# RPi_Extension_adc.net
KiCad netlist of a schematic drawn in EAGLE
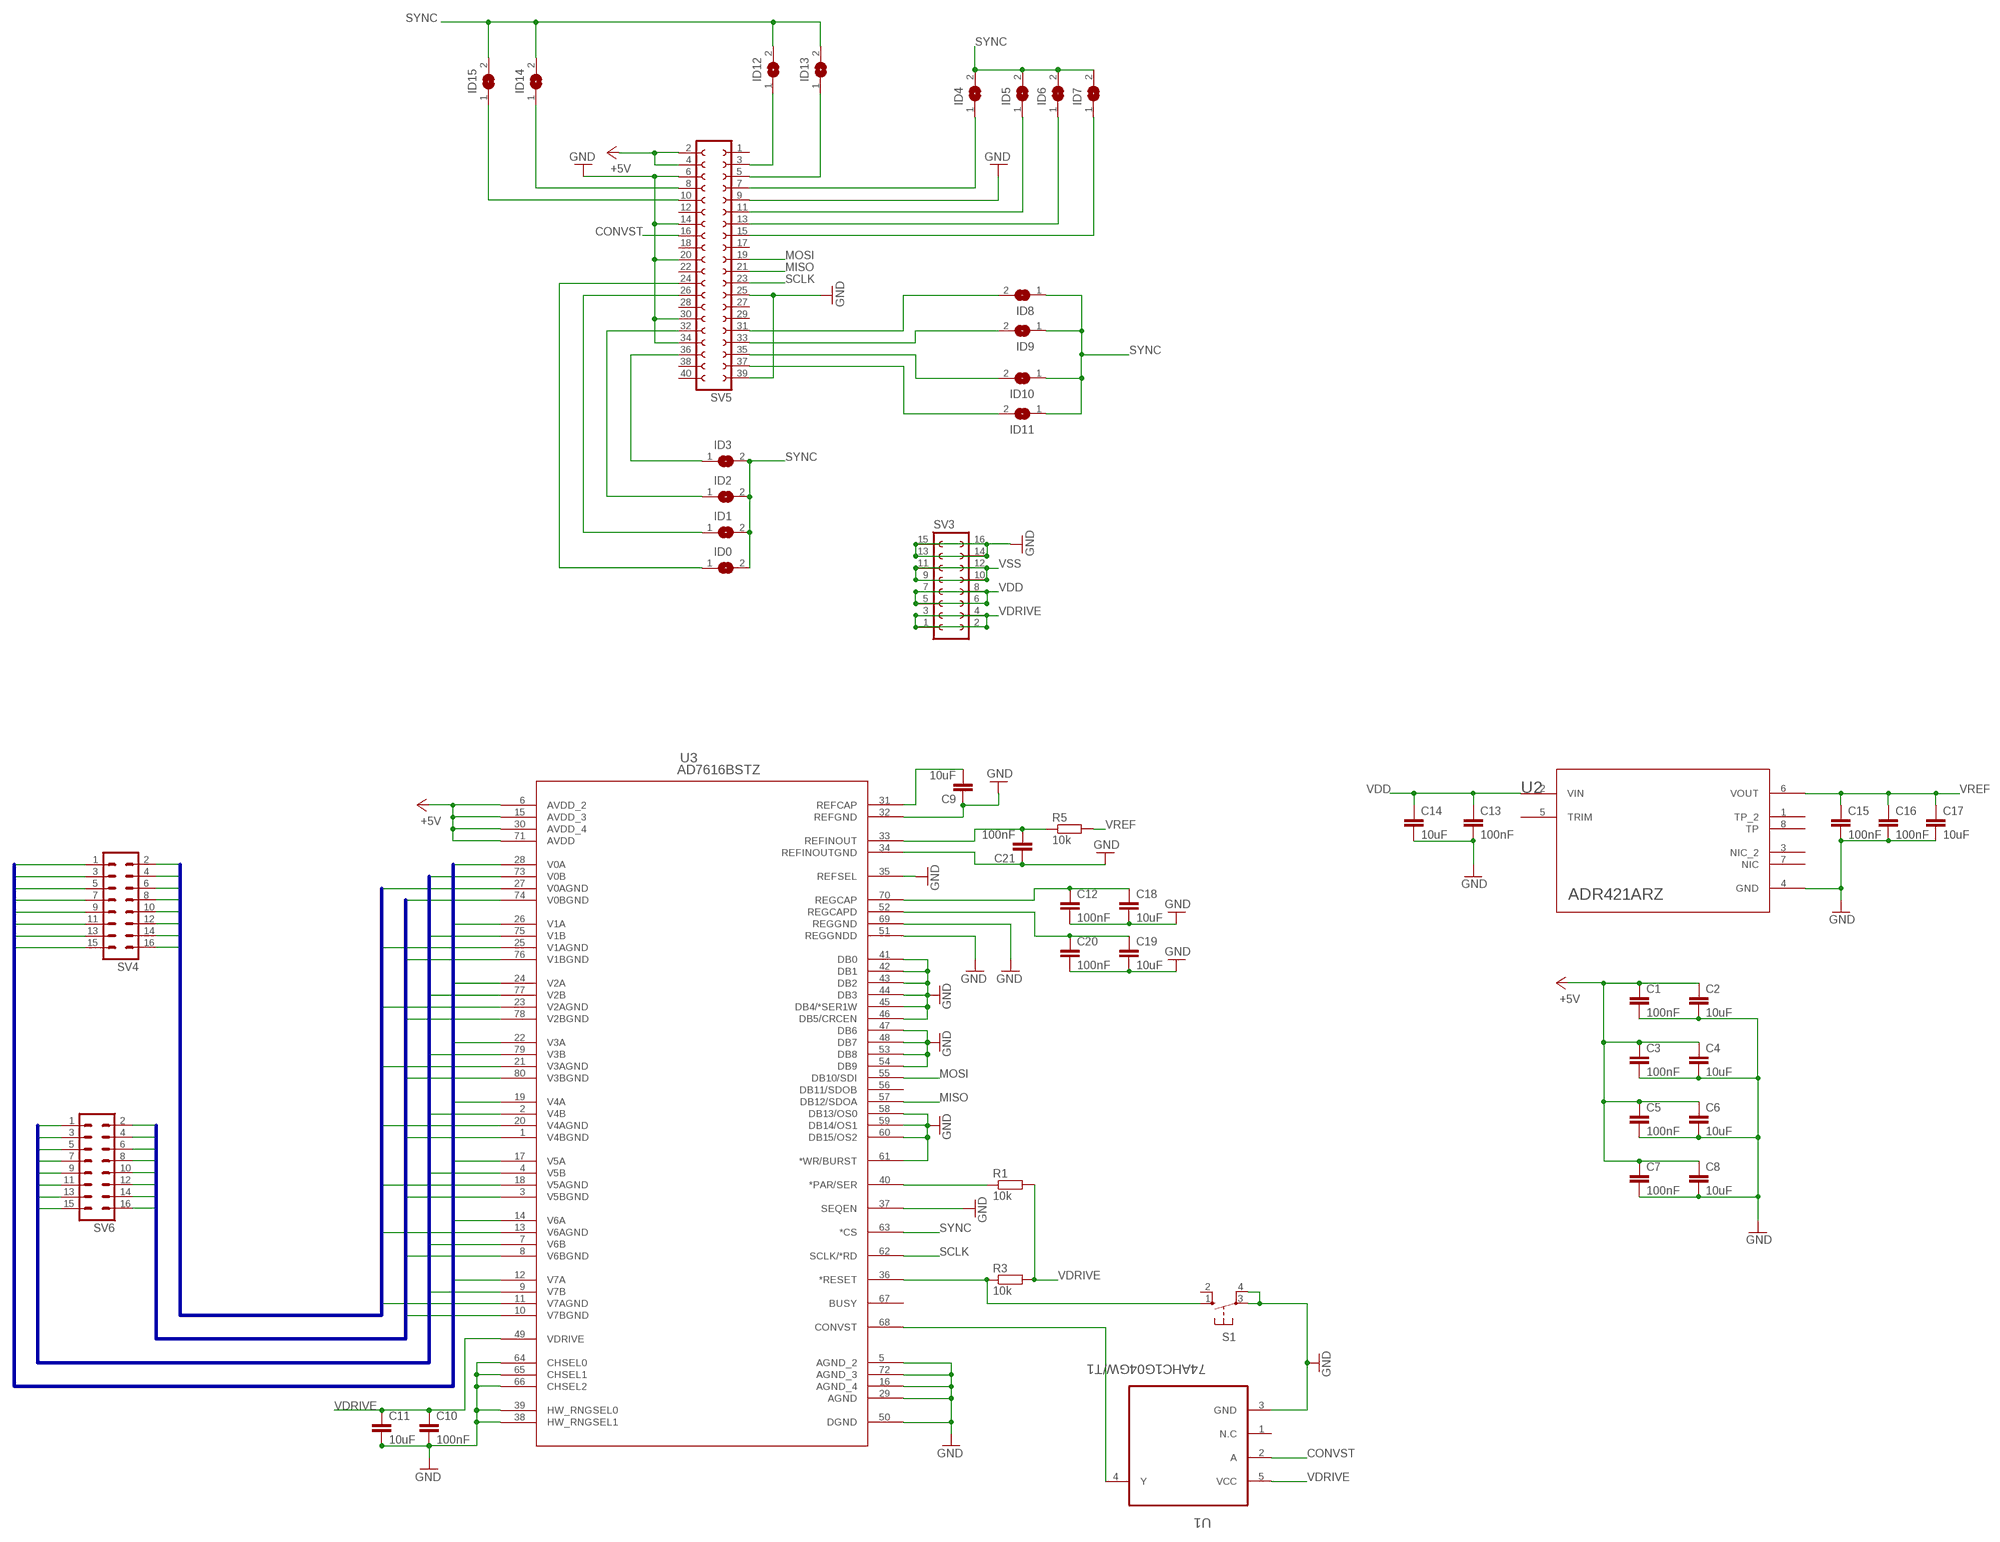
[diagram p0: schematic, sheet 1]

(export (version "E")
  (design (tool "Eeschema 10.0.6"))
  (components
    (comp (ref "C1")
      (value "100nF")
      (footprint "eagle-import:C0603")
      (libsource (lib "eagle-import") (part "C-EUC0603"))
    )
    (comp (ref "C2")
      (value "10uF")
      (footprint "eagle-import:C0603")
      (libsource (lib "eagle-import") (part "C-EUC0603"))
    )
    (comp (ref "C3")
      (value "100nF")
      (footprint "eagle-import:C0603")
      (libsource (lib "eagle-import") (part "C-EUC0603"))
    )
    (comp (ref "C4")
      (value "10uF")
      (footprint "eagle-import:C0603")
      (libsource (lib "eagle-import") (part "C-EUC0603"))
    )
    (comp (ref "C5")
      (value "100nF")
      (footprint "eagle-import:C0603")
      (libsource (lib "eagle-import") (part "C-EUC0603"))
    )
    (comp (ref "C6")
      (value "10uF")
      (footprint "eagle-import:C0603")
      (libsource (lib "eagle-import") (part "C-EUC0603"))
    )
    (comp (ref "C7")
      (value "100nF")
      (footprint "eagle-import:C0603")
      (libsource (lib "eagle-import") (part "C-EUC0603"))
    )
    (comp (ref "C8")
      (value "10uF")
      (footprint "eagle-import:C0603")
      (libsource (lib "eagle-import") (part "C-EUC0603"))
    )
    (comp (ref "C9")
      (value "10uF")
      (footprint "eagle-import:C0603")
      (libsource (lib "eagle-import") (part "C-EUC0603"))
    )
    (comp (ref "C10")
      (value "100nF")
      (footprint "eagle-import:C0603")
      (libsource (lib "eagle-import") (part "C-EUC0603"))
    )
    (comp (ref "C11")
      (value "10uF")
      (footprint "eagle-import:C0603")
      (libsource (lib "eagle-import") (part "C-EUC0603"))
    )
    (comp (ref "C12")
      (value "100nF")
      (footprint "eagle-import:C0603")
      (libsource (lib "eagle-import") (part "C-EUC0603"))
    )
    (comp (ref "C13")
      (value "100nF")
      (footprint "eagle-import:C0603")
      (libsource (lib "eagle-import") (part "C-EUC0603"))
    )
    (comp (ref "C14")
      (value "10uF")
      (footprint "eagle-import:C1206")
      (libsource (lib "eagle-import") (part "C-EUC1206"))
    )
    (comp (ref "C15")
      (value "100nF")
      (footprint "eagle-import:C0603")
      (libsource (lib "eagle-import") (part "C-EUC0603"))
    )
    (comp (ref "C16")
      (value "100nF")
      (footprint "eagle-import:C0603")
      (libsource (lib "eagle-import") (part "C-EUC0603"))
    )
    (comp (ref "C17")
      (value "10uF")
      (footprint "eagle-import:C1206")
      (libsource (lib "eagle-import") (part "C-EUC1206"))
    )
    (comp (ref "C18")
      (value "10uF")
      (footprint "eagle-import:C0603")
      (libsource (lib "eagle-import") (part "C-EUC0603"))
    )
    (comp (ref "C19")
      (value "10uF")
      (footprint "eagle-import:C0603")
      (libsource (lib "eagle-import") (part "C-EUC0603"))
    )
    (comp (ref "C20")
      (value "100nF")
      (footprint "eagle-import:C0603")
      (libsource (lib "eagle-import") (part "C-EUC0603"))
    )
    (comp (ref "C21")
      (value "100nF")
      (footprint "eagle-import:C0603")
      (libsource (lib "eagle-import") (part "C-EUC0603"))
    )
    (comp (ref "ID0") (value "SJ") (footprint "eagle-import:SJ") (libsource (lib "eagle-import") (part "SJ")))
    (comp (ref "ID1") (value "SJ") (footprint "eagle-import:SJ") (libsource (lib "eagle-import") (part "SJ")))
    (comp (ref "ID2") (value "SJ") (footprint "eagle-import:SJ") (libsource (lib "eagle-import") (part "SJ")))
    (comp (ref "ID3") (value "SJ") (footprint "eagle-import:SJ") (libsource (lib "eagle-import") (part "SJ")))
    (comp (ref "ID4") (value "SJ") (footprint "eagle-import:SJ") (libsource (lib "eagle-import") (part "SJ")))
    (comp (ref "ID5") (value "SJ") (footprint "eagle-import:SJ") (libsource (lib "eagle-import") (part "SJ")))
    (comp (ref "ID6") (value "SJ") (footprint "eagle-import:SJ") (libsource (lib "eagle-import") (part "SJ")))
    (comp (ref "ID7") (value "SJ") (footprint "eagle-import:SJ") (libsource (lib "eagle-import") (part "SJ")))
    (comp (ref "ID8") (value "SJ") (footprint "eagle-import:SJ") (libsource (lib "eagle-import") (part "SJ")))
    (comp (ref "ID9") (value "SJ") (footprint "eagle-import:SJ") (libsource (lib "eagle-import") (part "SJ")))
    (comp (ref "ID10")
      (value "SJ")
      (footprint "eagle-import:SJ")
      (libsource (lib "eagle-import") (part "SJ"))
    )
    (comp (ref "ID11")
      (value "SJ")
      (footprint "eagle-import:SJ")
      (libsource (lib "eagle-import") (part "SJ"))
    )
    (comp (ref "ID12")
      (value "SJ")
      (footprint "eagle-import:SJ")
      (libsource (lib "eagle-import") (part "SJ"))
    )
    (comp (ref "ID13")
      (value "SJ")
      (footprint "eagle-import:SJ")
      (libsource (lib "eagle-import") (part "SJ"))
    )
    (comp (ref "ID14")
      (value "SJ")
      (footprint "eagle-import:SJ")
      (libsource (lib "eagle-import") (part "SJ"))
    )
    (comp (ref "ID15")
      (value "SJ")
      (footprint "eagle-import:SJ")
      (libsource (lib "eagle-import") (part "SJ"))
    )
    (comp (ref "R1")
      (value "10k")
      (footprint "eagle-import:R0603")
      (libsource (lib "eagle-import") (part "R-EU_R0603"))
    )
    (comp (ref "R3")
      (value "10k")
      (footprint "eagle-import:R0603")
      (libsource (lib "eagle-import") (part "R-EU_R0603"))
    )
    (comp (ref "R5")
      (value "10k")
      (footprint "eagle-import:R0603")
      (libsource (lib "eagle-import") (part "R-EU_R0603"))
    )
    (comp (ref "S1")
      (value "10-XX")
      (footprint "eagle-import:B3F-10XX")
      (fields (field (name "MPN") "B3F-1000"))
      (libsource (lib "eagle-import") (part "10-XX"))
    )
    (comp (ref "SV3")
      (value "FE08-2")
      (footprint "eagle-import:FE08-2")
      (libsource (lib "eagle-import") (part "FE08-2"))
    )
    (comp (ref "SV4")
      (value "MA08-2W")
      (footprint "eagle-import:MA08-2W")
      (libsource (lib "eagle-import") (part "MA08-2W"))
    )
    (comp (ref "SV5")
      (value "FE20-2")
      (footprint "eagle-import:FE20-2")
      (libsource (lib "eagle-import") (part "FE20-2"))
    )
    (comp (ref "SV6")
      (value "MA08-2W")
      (footprint "eagle-import:MA08-2W")
      (libsource (lib "eagle-import") (part "MA08-2W"))
    )
    (comp (ref "U1")
      (value "74AHC1G04GW/T1")
      (footprint "eagle-import:SOT65P210X110-5N")
      (libsource (lib "eagle-import") (part "74AHC1G04GW/T1"))
    )
    (comp (ref "U2")
      (value "ADR421ARZ")
      (footprint "eagle-import:R_8")
      (fields (field (name "MANUFACTURER_PART_NUMBER") "ADR423ARZ"))
      (libsource (lib "eagle-import") (part "ADR423ARZ"))
    )
    (comp (ref "U3")
      (value "AD7616BSTZ")
      (footprint "eagle-import:ST_80_2")
      (libsource (lib "eagle-import") (part "AD7616BSTZ"))
    )
  )
  (nets
    (net (code "1") (name "+5V") (class "Default")
      (node (ref "C1") (pin "1") (pinfunction "1_1") (pintype "passive"))
      (node (ref "C2") (pin "1") (pinfunction "1_1") (pintype "passive"))
      (node (ref "C3") (pin "1") (pinfunction "1_1") (pintype "passive"))
      (node (ref "C4") (pin "1") (pinfunction "1_1") (pintype "passive"))
      (node (ref "C5") (pin "1") (pinfunction "1_1") (pintype "passive"))
      (node (ref "C6") (pin "1") (pinfunction "1_1") (pintype "passive"))
      (node (ref "C7") (pin "1") (pinfunction "1_1") (pintype "passive"))
      (node (ref "C8") (pin "1") (pinfunction "1_1") (pintype "passive"))
      (node (ref "SV5") (pin "2") (pinfunction "2_2") (pintype "passive"))
      (node (ref "SV5") (pin "4") (pinfunction "4_4") (pintype "passive"))
      (node (ref "U3") (pin "15") (pinfunction "AVDD_3_15") (pintype "passive"))
      (node (ref "U3") (pin "30") (pinfunction "AVDD_4_30") (pintype "passive"))
      (node (ref "U3") (pin "6") (pinfunction "AVDD_2_6") (pintype "passive"))
      (node (ref "U3") (pin "71") (pinfunction "AVDD_71") (pintype "passive"))
    )
    (net (code "2") (name "/CONVST") (class "Default")
      (node (ref "SV5") (pin "16") (pinfunction "16_16") (pintype "passive"))
      (node (ref "U1") (pin "2") (pinfunction "A_2") (pintype "input"))
    )
    (net (code "3") (name "/MISO") (class "Default")
      (node (ref "SV5") (pin "21") (pinfunction "21_21") (pintype "passive"))
      (node (ref "U3") (pin "57") (pinfunction "DB12/SDOA_57") (pintype "passive"))
    )
    (net (code "4") (name "/MOSI") (class "Default")
      (node (ref "SV5") (pin "19") (pinfunction "19_19") (pintype "passive"))
      (node (ref "U3") (pin "55") (pinfunction "DB10/SDI_55") (pintype "passive"))
    )
    (net (code "5") (name "/SCLK") (class "Default")
      (node (ref "SV5") (pin "23") (pinfunction "23_23") (pintype "passive"))
      (node (ref "U3") (pin "62") (pinfunction "SCLK/*RD_62") (pintype "passive"))
    )
    (net (code "6") (name "/SYNC") (class "Default")
      (node (ref "ID0") (pin "2") (pinfunction "2_2") (pintype "passive"))
      (node (ref "ID1") (pin "2") (pinfunction "2_2") (pintype "passive"))
      (node (ref "ID10") (pin "1") (pinfunction "1_1") (pintype "passive"))
      (node (ref "ID11") (pin "1") (pinfunction "1_1") (pintype "passive"))
      (node (ref "ID12") (pin "2") (pinfunction "2_2") (pintype "passive"))
      (node (ref "ID13") (pin "2") (pinfunction "2_2") (pintype "passive"))
      (node (ref "ID14") (pin "2") (pinfunction "2_2") (pintype "passive"))
      (node (ref "ID15") (pin "2") (pinfunction "2_2") (pintype "passive"))
      (node (ref "ID2") (pin "2") (pinfunction "2_2") (pintype "passive"))
      (node (ref "ID3") (pin "2") (pinfunction "2_2") (pintype "passive"))
      (node (ref "ID4") (pin "2") (pinfunction "2_2") (pintype "passive"))
      (node (ref "ID5") (pin "2") (pinfunction "2_2") (pintype "passive"))
      (node (ref "ID6") (pin "2") (pinfunction "2_2") (pintype "passive"))
      (node (ref "ID7") (pin "2") (pinfunction "2_2") (pintype "passive"))
      (node (ref "ID8") (pin "1") (pinfunction "1_1") (pintype "passive"))
      (node (ref "ID9") (pin "1") (pinfunction "1_1") (pintype "passive"))
      (node (ref "U3") (pin "63") (pinfunction "*CS_63") (pintype "passive"))
    )
    (net (code "7") (name "/VA_GND0") (class "Default")
      (node (ref "SV4") (pin "2") (pinfunction "2_2") (pintype "passive"))
      (node (ref "U3") (pin "27") (pinfunction "V0AGND_27") (pintype "passive"))
    )
    (net (code "8") (name "/VA_GND1") (class "Default")
      (node (ref "SV4") (pin "4") (pinfunction "4_4") (pintype "passive"))
      (node (ref "U3") (pin "25") (pinfunction "V1AGND_25") (pintype "passive"))
    )
    (net (code "9") (name "/VA_GND2") (class "Default")
      (node (ref "SV4") (pin "6") (pinfunction "6_6") (pintype "passive"))
      (node (ref "U3") (pin "23") (pinfunction "V2AGND_23") (pintype "passive"))
    )
    (net (code "10") (name "/VA_GND3") (class "Default")
      (node (ref "SV4") (pin "8") (pinfunction "8_8") (pintype "passive"))
      (node (ref "U3") (pin "21") (pinfunction "V3AGND_21") (pintype "passive"))
    )
    (net (code "11") (name "/VA_GND4") (class "Default")
      (node (ref "SV4") (pin "10") (pinfunction "10_10") (pintype "passive"))
      (node (ref "U3") (pin "20") (pinfunction "V4AGND_20") (pintype "passive"))
    )
    (net (code "12") (name "/VA_GND5") (class "Default")
      (node (ref "SV4") (pin "12") (pinfunction "12_12") (pintype "passive"))
      (node (ref "U3") (pin "18") (pinfunction "V5AGND_18") (pintype "passive"))
    )
    (net (code "13") (name "/VA_GND6") (class "Default")
      (node (ref "SV4") (pin "14") (pinfunction "14_14") (pintype "passive"))
      (node (ref "U3") (pin "13") (pinfunction "V6AGND_13") (pintype "passive"))
    )
    (net (code "14") (name "/VA_GND7") (class "Default")
      (node (ref "SV4") (pin "16") (pinfunction "16_16") (pintype "passive"))
      (node (ref "U3") (pin "11") (pinfunction "V7AGND_11") (pintype "passive"))
    )
    (net (code "15") (name "/VA_IN0") (class "Default")
      (node (ref "SV4") (pin "1") (pinfunction "1_1") (pintype "passive"))
      (node (ref "U3") (pin "28") (pinfunction "V0A_28") (pintype "passive"))
    )
    (net (code "16") (name "/VA_IN1") (class "Default")
      (node (ref "SV4") (pin "3") (pinfunction "3_3") (pintype "passive"))
      (node (ref "U3") (pin "26") (pinfunction "V1A_26") (pintype "passive"))
    )
    (net (code "17") (name "/VA_IN2") (class "Default")
      (node (ref "SV4") (pin "5") (pinfunction "5_5") (pintype "passive"))
      (node (ref "U3") (pin "24") (pinfunction "V2A_24") (pintype "passive"))
    )
    (net (code "18") (name "/VA_IN3") (class "Default")
      (node (ref "SV4") (pin "7") (pinfunction "7_7") (pintype "passive"))
      (node (ref "U3") (pin "22") (pinfunction "V3A_22") (pintype "passive"))
    )
    (net (code "19") (name "/VA_IN4") (class "Default")
      (node (ref "SV4") (pin "9") (pinfunction "9_9") (pintype "passive"))
      (node (ref "U3") (pin "19") (pinfunction "V4A_19") (pintype "passive"))
    )
    (net (code "20") (name "/VA_IN5") (class "Default")
      (node (ref "SV4") (pin "11") (pinfunction "11_11") (pintype "passive"))
      (node (ref "U3") (pin "17") (pinfunction "V5A_17") (pintype "passive"))
    )
    (net (code "21") (name "/VA_IN6") (class "Default")
      (node (ref "SV4") (pin "13") (pinfunction "13_13") (pintype "passive"))
      (node (ref "U3") (pin "14") (pinfunction "V6A_14") (pintype "passive"))
    )
    (net (code "22") (name "/VA_IN7") (class "Default")
      (node (ref "SV4") (pin "15") (pinfunction "15_15") (pintype "passive"))
      (node (ref "U3") (pin "12") (pinfunction "V7A_12") (pintype "passive"))
    )
    (net (code "23") (name "/VB_GND0") (class "Default")
      (node (ref "SV6") (pin "16") (pinfunction "16_16") (pintype "passive"))
      (node (ref "U3") (pin "74") (pinfunction "V0BGND_74") (pintype "passive"))
    )
    (net (code "24") (name "/VB_GND1") (class "Default")
      (node (ref "SV6") (pin "14") (pinfunction "14_14") (pintype "passive"))
      (node (ref "U3") (pin "76") (pinfunction "V1BGND_76") (pintype "passive"))
    )
    (net (code "25") (name "/VB_GND2") (class "Default")
      (node (ref "SV6") (pin "12") (pinfunction "12_12") (pintype "passive"))
      (node (ref "U3") (pin "78") (pinfunction "V2BGND_78") (pintype "passive"))
    )
    (net (code "26") (name "/VB_GND3") (class "Default")
      (node (ref "SV6") (pin "10") (pinfunction "10_10") (pintype "passive"))
      (node (ref "U3") (pin "80") (pinfunction "V3BGND_80") (pintype "passive"))
    )
    (net (code "27") (name "/VB_GND4") (class "Default")
      (node (ref "SV6") (pin "8") (pinfunction "8_8") (pintype "passive"))
      (node (ref "U3") (pin "1") (pinfunction "V4BGND_1") (pintype "passive"))
    )
    (net (code "28") (name "/VB_GND5") (class "Default")
      (node (ref "SV6") (pin "6") (pinfunction "6_6") (pintype "passive"))
      (node (ref "U3") (pin "3") (pinfunction "V5BGND_3") (pintype "passive"))
    )
    (net (code "29") (name "/VB_GND6") (class "Default")
      (node (ref "SV6") (pin "4") (pinfunction "4_4") (pintype "passive"))
      (node (ref "U3") (pin "8") (pinfunction "V6BGND_8") (pintype "passive"))
    )
    (net (code "30") (name "/VB_GND7") (class "Default")
      (node (ref "SV6") (pin "2") (pinfunction "2_2") (pintype "passive"))
      (node (ref "U3") (pin "10") (pinfunction "V7BGND_10") (pintype "passive"))
    )
    (net (code "31") (name "/VB_IN0") (class "Default")
      (node (ref "SV6") (pin "15") (pinfunction "15_15") (pintype "passive"))
      (node (ref "U3") (pin "73") (pinfunction "V0B_73") (pintype "passive"))
    )
    (net (code "32") (name "/VB_IN1") (class "Default")
      (node (ref "SV6") (pin "13") (pinfunction "13_13") (pintype "passive"))
      (node (ref "U3") (pin "75") (pinfunction "V1B_75") (pintype "passive"))
    )
    (net (code "33") (name "/VB_IN2") (class "Default")
      (node (ref "SV6") (pin "11") (pinfunction "11_11") (pintype "passive"))
      (node (ref "U3") (pin "77") (pinfunction "V2B_77") (pintype "passive"))
    )
    (net (code "34") (name "/VB_IN3") (class "Default")
      (node (ref "SV6") (pin "9") (pinfunction "9_9") (pintype "passive"))
      (node (ref "U3") (pin "79") (pinfunction "V3B_79") (pintype "passive"))
    )
    (net (code "35") (name "/VB_IN4") (class "Default")
      (node (ref "SV6") (pin "7") (pinfunction "7_7") (pintype "passive"))
      (node (ref "U3") (pin "2") (pinfunction "V4B_2") (pintype "passive"))
    )
    (net (code "36") (name "/VB_IN5") (class "Default")
      (node (ref "SV6") (pin "5") (pinfunction "5_5") (pintype "passive"))
      (node (ref "U3") (pin "4") (pinfunction "V5B_4") (pintype "passive"))
    )
    (net (code "37") (name "/VB_IN6") (class "Default")
      (node (ref "SV6") (pin "3") (pinfunction "3_3") (pintype "passive"))
      (node (ref "U3") (pin "7") (pinfunction "V6B_7") (pintype "passive"))
    )
    (net (code "38") (name "/VB_IN7") (class "Default")
      (node (ref "SV6") (pin "1") (pinfunction "1_1") (pintype "passive"))
      (node (ref "U3") (pin "9") (pinfunction "V7B_9") (pintype "passive"))
    )
    (net (code "39") (name "/VDD") (class "Default")
      (node (ref "C13") (pin "1") (pinfunction "1_1") (pintype "passive"))
      (node (ref "C14") (pin "1") (pinfunction "1_1") (pintype "passive"))
      (node (ref "SV3") (pin "5") (pinfunction "5_5") (pintype "passive"))
      (node (ref "SV3") (pin "6") (pinfunction "6_6") (pintype "passive"))
      (node (ref "SV3") (pin "7") (pinfunction "7_7") (pintype "passive"))
      (node (ref "SV3") (pin "8") (pinfunction "8_8") (pintype "passive"))
      (node (ref "U2") (pin "2") (pinfunction "VIN_2") (pintype "passive"))
    )
    (net (code "40") (name "/VDRIVE") (class "Default")
      (node (ref "C10") (pin "1") (pinfunction "1_1") (pintype "passive"))
      (node (ref "C11") (pin "1") (pinfunction "1_1") (pintype "passive"))
      (node (ref "R1") (pin "2") (pinfunction "2_2") (pintype "passive"))
      (node (ref "R3") (pin "2") (pinfunction "2_2") (pintype "passive"))
      (node (ref "SV3") (pin "1") (pinfunction "1_1") (pintype "passive"))
      (node (ref "SV3") (pin "2") (pinfunction "2_2") (pintype "passive"))
      (node (ref "SV3") (pin "3") (pinfunction "3_3") (pintype "passive"))
      (node (ref "SV3") (pin "4") (pinfunction "4_4") (pintype "passive"))
      (node (ref "U1") (pin "5") (pinfunction "VCC_5") (pintype "power_in"))
      (node (ref "U3") (pin "49") (pinfunction "VDRIVE_49") (pintype "passive"))
    )
    (net (code "41") (name "/VREF") (class "Default")
      (node (ref "C15") (pin "1") (pinfunction "1_1") (pintype "passive"))
      (node (ref "C16") (pin "1") (pinfunction "1_1") (pintype "passive"))
      (node (ref "C17") (pin "1") (pinfunction "1_1") (pintype "passive"))
      (node (ref "R5") (pin "2") (pinfunction "2_2") (pintype "passive"))
      (node (ref "U2") (pin "6") (pinfunction "VOUT_6") (pintype "passive"))
    )
    (net (code "42") (name "/VSS") (class "Default")
      (node (ref "SV3") (pin "10") (pinfunction "10_10") (pintype "passive"))
      (node (ref "SV3") (pin "11") (pinfunction "11_11") (pintype "passive"))
      (node (ref "SV3") (pin "12") (pinfunction "12_12") (pintype "passive"))
      (node (ref "SV3") (pin "9") (pinfunction "9_9") (pintype "passive"))
    )
    (net (code "43") (name "GND") (class "Default")
      (node (ref "C1") (pin "2") (pinfunction "2_2") (pintype "passive"))
      (node (ref "C10") (pin "2") (pinfunction "2_2") (pintype "passive"))
      (node (ref "C11") (pin "2") (pinfunction "2_2") (pintype "passive"))
      (node (ref "C12") (pin "2") (pinfunction "2_2") (pintype "passive"))
      (node (ref "C13") (pin "2") (pinfunction "2_2") (pintype "passive"))
      (node (ref "C14") (pin "2") (pinfunction "2_2") (pintype "passive"))
      (node (ref "C15") (pin "2") (pinfunction "2_2") (pintype "passive"))
      (node (ref "C16") (pin "2") (pinfunction "2_2") (pintype "passive"))
      (node (ref "C17") (pin "2") (pinfunction "2_2") (pintype "passive"))
      (node (ref "C18") (pin "2") (pinfunction "2_2") (pintype "passive"))
      (node (ref "C19") (pin "2") (pinfunction "2_2") (pintype "passive"))
      (node (ref "C2") (pin "2") (pinfunction "2_2") (pintype "passive"))
      (node (ref "C20") (pin "2") (pinfunction "2_2") (pintype "passive"))
      (node (ref "C21") (pin "1") (pinfunction "1_1") (pintype "passive"))
      (node (ref "C3") (pin "2") (pinfunction "2_2") (pintype "passive"))
      (node (ref "C4") (pin "2") (pinfunction "2_2") (pintype "passive"))
      (node (ref "C5") (pin "2") (pinfunction "2_2") (pintype "passive"))
      (node (ref "C6") (pin "2") (pinfunction "2_2") (pintype "passive"))
      (node (ref "C7") (pin "2") (pinfunction "2_2") (pintype "passive"))
      (node (ref "C8") (pin "2") (pinfunction "2_2") (pintype "passive"))
      (node (ref "C9") (pin "1") (pinfunction "1_1") (pintype "passive"))
      (node (ref "S1") (pin "3") (pinfunction "P_3") (pintype "passive"))
      (node (ref "S1") (pin "4") (pinfunction "P1_4") (pintype "passive"))
      (node (ref "SV3") (pin "13") (pinfunction "13_13") (pintype "passive"))
      (node (ref "SV3") (pin "14") (pinfunction "14_14") (pintype "passive"))
      (node (ref "SV3") (pin "15") (pinfunction "15_15") (pintype "passive"))
      (node (ref "SV3") (pin "16") (pinfunction "16_16") (pintype "passive"))
      (node (ref "SV5") (pin "14") (pinfunction "14_14") (pintype "passive"))
      (node (ref "SV5") (pin "20") (pinfunction "20_20") (pintype "passive"))
      (node (ref "SV5") (pin "25") (pinfunction "25_25") (pintype "passive"))
      (node (ref "SV5") (pin "30") (pinfunction "30_30") (pintype "passive"))
      (node (ref "SV5") (pin "34") (pinfunction "34_34") (pintype "passive"))
      (node (ref "SV5") (pin "39") (pinfunction "39_39") (pintype "passive"))
      (node (ref "SV5") (pin "6") (pinfunction "6_6") (pintype "passive"))
      (node (ref "SV5") (pin "9") (pinfunction "9_9") (pintype "passive"))
      (node (ref "U1") (pin "3") (pinfunction "GND_3") (pintype "passive"))
      (node (ref "U2") (pin "4") (pinfunction "GND_4") (pintype "passive"))
      (node (ref "U3") (pin "16") (pinfunction "AGND_4_16") (pintype "passive"))
      (node (ref "U3") (pin "29") (pinfunction "AGND_29") (pintype "passive"))
      (node (ref "U3") (pin "32") (pinfunction "REFGND_32") (pintype "passive"))
      (node (ref "U3") (pin "34") (pinfunction "REFINOUTGND_34") (pintype "passive"))
      (node (ref "U3") (pin "35") (pinfunction "REFSEL_35") (pintype "passive"))
      (node (ref "U3") (pin "37") (pinfunction "SEQEN_37") (pintype "passive"))
      (node (ref "U3") (pin "38") (pinfunction "HW_RNGSEL1_38") (pintype "passive"))
      (node (ref "U3") (pin "39") (pinfunction "HW_RNGSEL0_39") (pintype "passive"))
      (node (ref "U3") (pin "41") (pinfunction "DB0_41") (pintype "passive"))
      (node (ref "U3") (pin "42") (pinfunction "DB1_42") (pintype "passive"))
      (node (ref "U3") (pin "43") (pinfunction "DB2_43") (pintype "passive"))
      (node (ref "U3") (pin "44") (pinfunction "DB3_44") (pintype "passive"))
      (node (ref "U3") (pin "45") (pinfunction "DB4/*SER1W_45") (pintype "passive"))
      (node (ref "U3") (pin "46") (pinfunction "DB5/CRCEN_46") (pintype "passive"))
      (node (ref "U3") (pin "47") (pinfunction "DB6_47") (pintype "passive"))
      (node (ref "U3") (pin "48") (pinfunction "DB7_48") (pintype "passive"))
      (node (ref "U3") (pin "5") (pinfunction "AGND_2_5") (pintype "passive"))
      (node (ref "U3") (pin "50") (pinfunction "DGND_50") (pintype "passive"))
      (node (ref "U3") (pin "51") (pinfunction "REGGNDD_51") (pintype "passive"))
      (node (ref "U3") (pin "53") (pinfunction "DB8_53") (pintype "passive"))
      (node (ref "U3") (pin "54") (pinfunction "DB9_54") (pintype "passive"))
      (node (ref "U3") (pin "58") (pinfunction "DB13/OS0_58") (pintype "passive"))
      (node (ref "U3") (pin "59") (pinfunction "DB14/OS1_59") (pintype "passive"))
      (node (ref "U3") (pin "60") (pinfunction "DB15/OS2_60") (pintype "passive"))
      (node (ref "U3") (pin "61") (pinfunction "*WR/BURST_61") (pintype "passive"))
      (node (ref "U3") (pin "64") (pinfunction "CHSEL0_64") (pintype "passive"))
      (node (ref "U3") (pin "65") (pinfunction "CHSEL1_65") (pintype "passive"))
      (node (ref "U3") (pin "66") (pinfunction "CHSEL2_66") (pintype "passive"))
      (node (ref "U3") (pin "69") (pinfunction "REGGND_69") (pintype "passive"))
      (node (ref "U3") (pin "72") (pinfunction "AGND_3_72") (pintype "passive"))
    )
    (net (code "44") (name "Net-(ID0-Pad1)") (class "Default")
      (node (ref "ID0") (pin "1") (pinfunction "1_1") (pintype "passive"))
      (node (ref "SV5") (pin "24") (pinfunction "24_24") (pintype "passive"))
    )
    (net (code "45") (name "Net-(ID1-Pad1)") (class "Default")
      (node (ref "ID1") (pin "1") (pinfunction "1_1") (pintype "passive"))
      (node (ref "SV5") (pin "26") (pinfunction "26_26") (pintype "passive"))
    )
    (net (code "46") (name "Net-(ID2-Pad1)") (class "Default")
      (node (ref "ID2") (pin "1") (pinfunction "1_1") (pintype "passive"))
      (node (ref "SV5") (pin "32") (pinfunction "32_32") (pintype "passive"))
    )
    (net (code "47") (name "Net-(ID3-Pad1)") (class "Default")
      (node (ref "ID3") (pin "1") (pinfunction "1_1") (pintype "passive"))
      (node (ref "SV5") (pin "36") (pinfunction "36_36") (pintype "passive"))
    )
    (net (code "48") (name "Net-(ID4-Pad1)") (class "Default")
      (node (ref "ID4") (pin "1") (pinfunction "1_1") (pintype "passive"))
      (node (ref "SV5") (pin "7") (pinfunction "7_7") (pintype "passive"))
    )
    (net (code "49") (name "Net-(ID5-Pad1)") (class "Default")
      (node (ref "ID5") (pin "1") (pinfunction "1_1") (pintype "passive"))
      (node (ref "SV5") (pin "11") (pinfunction "11_11") (pintype "passive"))
    )
    (net (code "50") (name "Net-(ID6-Pad1)") (class "Default")
      (node (ref "ID6") (pin "1") (pinfunction "1_1") (pintype "passive"))
      (node (ref "SV5") (pin "13") (pinfunction "13_13") (pintype "passive"))
    )
    (net (code "51") (name "Net-(ID7-Pad1)") (class "Default")
      (node (ref "ID7") (pin "1") (pinfunction "1_1") (pintype "passive"))
      (node (ref "SV5") (pin "15") (pinfunction "15_15") (pintype "passive"))
    )
    (net (code "52") (name "Net-(ID8-Pad2)") (class "Default")
      (node (ref "ID8") (pin "2") (pinfunction "2_2") (pintype "passive"))
      (node (ref "SV5") (pin "31") (pinfunction "31_31") (pintype "passive"))
    )
    (net (code "53") (name "Net-(ID9-Pad2)") (class "Default")
      (node (ref "ID9") (pin "2") (pinfunction "2_2") (pintype "passive"))
      (node (ref "SV5") (pin "33") (pinfunction "33_33") (pintype "passive"))
    )
    (net (code "54") (name "Net-(ID10-Pad2)") (class "Default")
      (node (ref "ID10") (pin "2") (pinfunction "2_2") (pintype "passive"))
      (node (ref "SV5") (pin "35") (pinfunction "35_35") (pintype "passive"))
    )
    (net (code "55") (name "Net-(ID11-Pad2)") (class "Default")
      (node (ref "ID11") (pin "2") (pinfunction "2_2") (pintype "passive"))
      (node (ref "SV5") (pin "37") (pinfunction "37_37") (pintype "passive"))
    )
    (net (code "56") (name "Net-(ID12-Pad1)") (class "Default")
      (node (ref "ID12") (pin "1") (pinfunction "1_1") (pintype "passive"))
      (node (ref "SV5") (pin "3") (pinfunction "3_3") (pintype "passive"))
    )
    (net (code "57") (name "Net-(ID13-Pad1)") (class "Default")
      (node (ref "ID13") (pin "1") (pinfunction "1_1") (pintype "passive"))
      (node (ref "SV5") (pin "5") (pinfunction "5_5") (pintype "passive"))
    )
    (net (code "58") (name "Net-(ID14-Pad1)") (class "Default")
      (node (ref "ID14") (pin "1") (pinfunction "1_1") (pintype "passive"))
      (node (ref "SV5") (pin "8") (pinfunction "8_8") (pintype "passive"))
    )
    (net (code "59") (name "Net-(ID15-Pad1)") (class "Default")
      (node (ref "ID15") (pin "1") (pinfunction "1_1") (pintype "passive"))
      (node (ref "SV5") (pin "10") (pinfunction "10_10") (pintype "passive"))
    )
    (net (code "60") (name "Net-(S1-S)") (class "Default")
      (node (ref "R3") (pin "1") (pinfunction "1_1") (pintype "passive"))
      (node (ref "S1") (pin "1") (pinfunction "S_1") (pintype "passive"))
      (node (ref "U3") (pin "36") (pinfunction "*RESET_36") (pintype "passive"))
    )
    (net (code "61") (name "Net-(U1-Y)") (class "Default")
      (node (ref "U1") (pin "4") (pinfunction "Y_4") (pintype "output"))
      (node (ref "U3") (pin "68") (pinfunction "CONVST_68") (pintype "passive"))
    )
    (net (code "62") (name "Net-(U3-*PAR{slash}SER)") (class "Default")
      (node (ref "R1") (pin "1") (pinfunction "1_1") (pintype "passive"))
      (node (ref "U3") (pin "40") (pinfunction "*PAR/SER_40") (pintype "passive"))
    )
    (net (code "63") (name "Net-(U3-REFCAP)") (class "Default")
      (node (ref "C9") (pin "2") (pinfunction "2_2") (pintype "passive"))
      (node (ref "U3") (pin "31") (pinfunction "REFCAP_31") (pintype "passive"))
    )
    (net (code "64") (name "Net-(U3-REFINOUT)") (class "Default")
      (node (ref "C21") (pin "2") (pinfunction "2_2") (pintype "passive"))
      (node (ref "R5") (pin "1") (pinfunction "1_1") (pintype "passive"))
      (node (ref "U3") (pin "33") (pinfunction "REFINOUT_33") (pintype "passive"))
    )
    (net (code "65") (name "Net-(U3-REGCAP)") (class "Default")
      (node (ref "C12") (pin "1") (pinfunction "1_1") (pintype "passive"))
      (node (ref "C18") (pin "1") (pinfunction "1_1") (pintype "passive"))
      (node (ref "U3") (pin "70") (pinfunction "REGCAP_70") (pintype "passive"))
    )
    (net (code "66") (name "Net-(U3-REGCAPD)") (class "Default")
      (node (ref "C19") (pin "1") (pinfunction "1_1") (pintype "passive"))
      (node (ref "C20") (pin "1") (pinfunction "1_1") (pintype "passive"))
      (node (ref "U3") (pin "52") (pinfunction "REGCAPD_52") (pintype "passive"))
    )
    (net (code "67") (name "unconnected-(S1-S1-Pad2)") (class "Default")
      (node (ref "S1") (pin "2") (pinfunction "S1_2") (pintype "passive"))
    )
    (net (code "68") (name "unconnected-(SV5-Pad1)") (class "Default")
      (node (ref "SV5") (pin "1") (pinfunction "1_1") (pintype "passive"))
    )
    (net (code "69") (name "unconnected-(SV5-Pad12)") (class "Default")
      (node (ref "SV5") (pin "12") (pinfunction "12_12") (pintype "passive"))
    )
    (net (code "70") (name "unconnected-(SV5-Pad17)") (class "Default")
      (node (ref "SV5") (pin "17") (pinfunction "17_17") (pintype "passive"))
    )
    (net (code "71") (name "unconnected-(SV5-Pad18)") (class "Default")
      (node (ref "SV5") (pin "18") (pinfunction "18_18") (pintype "passive"))
    )
    (net (code "72") (name "unconnected-(SV5-Pad22)") (class "Default")
      (node (ref "SV5") (pin "22") (pinfunction "22_22") (pintype "passive"))
    )
    (net (code "73") (name "unconnected-(SV5-Pad27)") (class "Default")
      (node (ref "SV5") (pin "27") (pinfunction "27_27") (pintype "passive"))
    )
    (net (code "74") (name "unconnected-(SV5-Pad28)") (class "Default")
      (node (ref "SV5") (pin "28") (pinfunction "28_28") (pintype "passive"))
    )
    (net (code "75") (name "unconnected-(SV5-Pad29)") (class "Default")
      (node (ref "SV5") (pin "29") (pinfunction "29_29") (pintype "passive"))
    )
    (net (code "76") (name "unconnected-(SV5-Pad38)") (class "Default")
      (node (ref "SV5") (pin "38") (pinfunction "38_38") (pintype "passive"))
    )
    (net (code "77") (name "unconnected-(SV5-Pad40)") (class "Default")
      (node (ref "SV5") (pin "40") (pinfunction "40_40") (pintype "passive"))
    )
    (net (code "78") (name "unconnected-(U1-N.C-Pad1)") (class "Default")
      (node (ref "U1") (pin "1") (pinfunction "N.C_1") (pintype "no_connect"))
    )
    (net (code "79") (name "unconnected-(U2-NIC-Pad7)") (class "Default")
      (node (ref "U2") (pin "7") (pinfunction "NIC_7") (pintype "passive"))
    )
    (net (code "80") (name "unconnected-(U2-NIC_2-Pad3)") (class "Default")
      (node (ref "U2") (pin "3") (pinfunction "NIC_2_3") (pintype "passive"))
    )
    (net (code "81") (name "unconnected-(U2-TP-Pad8)") (class "Default")
      (node (ref "U2") (pin "8") (pinfunction "TP_8") (pintype "passive"))
    )
    (net (code "82") (name "unconnected-(U2-TP_2-Pad1)") (class "Default")
      (node (ref "U2") (pin "1") (pinfunction "TP_2_1") (pintype "passive"))
    )
    (net (code "83") (name "unconnected-(U2-TRIM-Pad5)") (class "Default")
      (node (ref "U2") (pin "5") (pinfunction "TRIM_5") (pintype "passive"))
    )
    (net (code "84") (name "unconnected-(U3-BUSY-Pad67)") (class "Default")
      (node (ref "U3") (pin "67") (pinfunction "BUSY_67") (pintype "passive"))
    )
    (net (code "85") (name "unconnected-(U3-DB11{slash}SDOB-Pad56)") (class "Default")
      (node (ref "U3") (pin "56") (pinfunction "DB11/SDOB_56") (pintype "passive"))
    )
  )
)
